# sinket.net
KiCad netlist of a schematic drawn in EAGLE
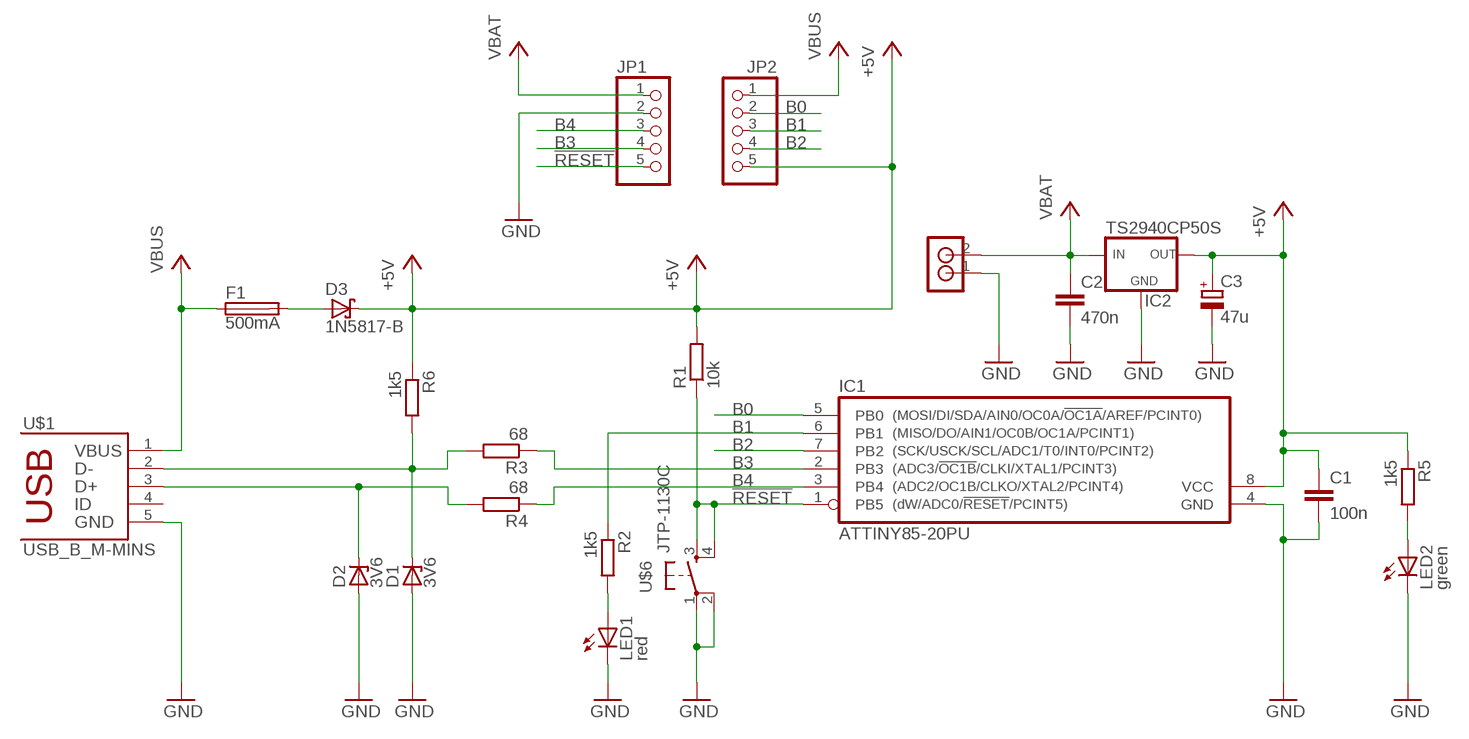
[diagram p0: schematic, sheet 1]

(export (version "E")
  (design (tool "Eeschema 10.0.6"))
  (components
    (comp (ref "C1")
      (value "100n")
      (footprint "eagle-import:C1206")
      (libsource (lib "eagle-import") (part "C-EUC1206"))
    )
    (comp (ref "C2")
      (value "470n")
      (footprint "eagle-import:C025-030X050")
      (libsource (lib "eagle-import") (part "C-EU025-030X050"))
    )
    (comp (ref "C3")
      (value "47u")
      (footprint "eagle-import:E2,5-6")
      (libsource (lib "eagle-import") (part "CPOL-EUE2.5-6"))
    )
    (comp (ref "D1")
      (value "3V6")
      (footprint "eagle-import:SOD80C")
      (libsource (lib "eagle-import") (part "ZENER-DIODESOD80C"))
    )
    (comp (ref "D2")
      (value "3V6")
      (footprint "eagle-import:SOD80C")
      (libsource (lib "eagle-import") (part "ZENER-DIODESOD80C"))
    )
    (comp (ref "D3")
      (value "1N5817-B")
      (footprint "eagle-import:DO41-7.6")
      (libsource (lib "eagle-import") (part "1N5817-B"))
    )
    (comp (ref "F1")
      (value "500mA")
      (footprint "eagle-import:LP60-050")
      (libsource (lib "eagle-import") (part "PTC-FUSE-LP60-050"))
    )
    (comp (ref "IC1")
      (value "ATTINY85-20PU")
      (footprint "eagle-import:8P3")
      (libsource (lib "eagle-import") (part "ATTINY25PU-20"))
    )
    (comp (ref "IC2")
      (value "TS2940CP50S")
      (footprint "eagle-import:TO-252")
      (libsource (lib "eagle-import") (part "TS2940SCP50"))
    )
    (comp (ref "JP1")
      (value "PINHD-1X5")
      (footprint "eagle-import:1X05")
      (libsource (lib "eagle-import") (part "PINHD-1X5"))
    )
    (comp (ref "JP2")
      (value "PINHD-1X5")
      (footprint "eagle-import:1X05")
      (libsource (lib "eagle-import") (part "PINHD-1X5"))
    )
    (comp (ref "LED1")
      (value "red")
      (footprint "eagle-import:LED5MM")
      (libsource (lib "eagle-import") (part "LED5MM"))
    )
    (comp (ref "LED2")
      (value "green")
      (footprint "eagle-import:LED5MM")
      (libsource (lib "eagle-import") (part "LED5MM"))
    )
    (comp (ref "R1")
      (value "10k")
      (footprint "eagle-import:R1206")
      (libsource (lib "eagle-import") (part "R-EU_R1206"))
    )
    (comp (ref "R2")
      (value "1k5")
      (footprint "eagle-import:R1206")
      (libsource (lib "eagle-import") (part "R-EU_R1206"))
    )
    (comp (ref "R3")
      (value "68")
      (footprint "eagle-import:R1206")
      (libsource (lib "eagle-import") (part "R-EU_R1206"))
    )
    (comp (ref "R4")
      (value "68")
      (footprint "eagle-import:R1206")
      (libsource (lib "eagle-import") (part "R-EU_R1206"))
    )
    (comp (ref "R5")
      (value "1k5")
      (footprint "eagle-import:R1206")
      (libsource (lib "eagle-import") (part "R-EU_R1206"))
    )
    (comp (ref "R6")
      (value "1k5")
      (footprint "eagle-import:R1206")
      (libsource (lib "eagle-import") (part "R-EU_R1206"))
    )
    (comp (ref "U$1")
      (value "USB_B_M-MINS")
      (footprint "eagle-import:LUMBERG_2486-01")
      (libsource (lib "eagle-import") (part "USB_B_M-MINS"))
    )
    (comp (ref "U$6")
      (value "JTP-1130C")
      (footprint "eagle-import:JTP-1130")
      (libsource (lib "eagle-import") (part "JTP-1130C"))
    )
    (comp (ref "U$7")
      (value "RIACON_101_2")
      (footprint "eagle-import:RIACON_101_2")
      (libsource (lib "eagle-import") (part "RIACON_101_2"))
    )
  )
  (nets
    (net (code "1") (name "+5V") (class "Default")
      (node (ref "C1") (pin "1") (pinfunction "1_1") (pintype "passive"))
      (node (ref "C3") (pin "+") (pinfunction "+_+") (pintype "passive"))
      (node (ref "D3") (pin "C") (pinfunction "C_C") (pintype "passive"))
      (node (ref "IC1") (pin "8") (pinfunction "VCC_8") (pintype "power_in"))
      (node (ref "IC2") (pin "3") (pinfunction "OUT_3") (pintype "power_in"))
      (node (ref "JP2") (pin "5") (pinfunction "5_5") (pintype "passive"))
      (node (ref "R1") (pin "2") (pinfunction "2_2") (pintype "passive"))
      (node (ref "R5") (pin "1") (pinfunction "1_1") (pintype "passive"))
      (node (ref "R6") (pin "1") (pinfunction "1_1") (pintype "passive"))
    )
    (net (code "2") (name "/B0") (class "Default")
      (node (ref "IC1") (pin "5") (pinfunction "PB0_5") (pintype "bidirectional"))
      (node (ref "JP2") (pin "2") (pinfunction "2_2") (pintype "passive"))
    )
    (net (code "3") (name "/B1") (class "Default")
      (node (ref "IC1") (pin "6") (pinfunction "PB1_6") (pintype "bidirectional"))
      (node (ref "JP2") (pin "3") (pinfunction "3_3") (pintype "passive"))
      (node (ref "R2") (pin "1") (pinfunction "1_1") (pintype "passive"))
    )
    (net (code "4") (name "/B2") (class "Default")
      (node (ref "IC1") (pin "7") (pinfunction "PB2_7") (pintype "bidirectional"))
      (node (ref "JP2") (pin "4") (pinfunction "4_4") (pintype "passive"))
    )
    (net (code "5") (name "/B3") (class "Default")
      (node (ref "IC1") (pin "2") (pinfunction "PB3_2") (pintype "bidirectional"))
      (node (ref "JP1") (pin "4") (pinfunction "4_4") (pintype "passive"))
      (node (ref "R3") (pin "1") (pinfunction "1_1") (pintype "passive"))
    )
    (net (code "6") (name "/B4") (class "Default")
      (node (ref "IC1") (pin "3") (pinfunction "PB4_3") (pintype "bidirectional"))
      (node (ref "JP1") (pin "3") (pinfunction "3_3") (pintype "passive"))
      (node (ref "R4") (pin "1") (pinfunction "1_1") (pintype "passive"))
    )
    (net (code "7") (name "/~{RESET}") (class "Default")
      (node (ref "IC1") (pin "1") (pinfunction "PB5_1") (pintype "bidirectional"))
      (node (ref "JP1") (pin "5") (pinfunction "5_5") (pintype "passive"))
      (node (ref "R1") (pin "1") (pinfunction "1_1") (pintype "passive"))
      (node (ref "U$6") (pin "3") (pinfunction "S_3") (pintype "passive"))
      (node (ref "U$6") (pin "4") (pinfunction "S1_4") (pintype "passive"))
    )
    (net (code "8") (name "GND") (class "Default")
      (node (ref "C1") (pin "2") (pinfunction "2_2") (pintype "passive"))
      (node (ref "C2") (pin "2") (pinfunction "2_2") (pintype "passive"))
      (node (ref "C3") (pin "-") (pinfunction "-_-") (pintype "passive"))
      (node (ref "D1") (pin "A") (pinfunction "A_A") (pintype "passive"))
      (node (ref "D2") (pin "A") (pinfunction "A_A") (pintype "passive"))
      (node (ref "IC1") (pin "4") (pinfunction "GND_4") (pintype "power_in"))
      (node (ref "IC2") (pin "2") (pinfunction "GND_2") (pintype "power_in"))
      (node (ref "JP1") (pin "2") (pinfunction "2_2") (pintype "passive"))
      (node (ref "LED1") (pin "K") (pinfunction "C_K") (pintype "passive"))
      (node (ref "LED2") (pin "K") (pinfunction "C_K") (pintype "passive"))
      (node (ref "U$1") (pin "5") (pinfunction "5_5") (pintype "passive"))
      (node (ref "U$6") (pin "1") (pinfunction "P_1") (pintype "passive"))
      (node (ref "U$6") (pin "2") (pinfunction "P1_2") (pintype "passive"))
      (node (ref "U$7") (pin "1") (pinfunction "1_1") (pintype "passive"))
    )
    (net (code "9") (name "Net-(D1-PadC)") (class "Default")
      (node (ref "D1") (pin "C") (pinfunction "C_C") (pintype "passive"))
      (node (ref "R3") (pin "2") (pinfunction "2_2") (pintype "passive"))
      (node (ref "R6") (pin "2") (pinfunction "2_2") (pintype "passive"))
      (node (ref "U$1") (pin "2") (pinfunction "2_2") (pintype "passive"))
    )
    (net (code "10") (name "Net-(D2-PadC)") (class "Default")
      (node (ref "D2") (pin "C") (pinfunction "C_C") (pintype "passive"))
      (node (ref "R4") (pin "2") (pinfunction "2_2") (pintype "passive"))
      (node (ref "U$1") (pin "3") (pinfunction "3_3") (pintype "passive"))
    )
    (net (code "11") (name "Net-(F1-2)") (class "Default")
      (node (ref "D3") (pin "A") (pinfunction "A_A") (pintype "passive"))
      (node (ref "F1") (pin "P$2") (pinfunction "2_P$2") (pintype "passive"))
    )
    (net (code "12") (name "Net-(LED1-PadA)") (class "Default")
      (node (ref "LED1") (pin "A") (pinfunction "A_A") (pintype "passive"))
      (node (ref "R2") (pin "2") (pinfunction "2_2") (pintype "passive"))
    )
    (net (code "13") (name "Net-(LED2-PadA)") (class "Default")
      (node (ref "LED2") (pin "A") (pinfunction "A_A") (pintype "passive"))
      (node (ref "R5") (pin "2") (pinfunction "2_2") (pintype "passive"))
    )
    (net (code "14") (name "VBAT") (class "Default")
      (node (ref "C2") (pin "1") (pinfunction "1_1") (pintype "passive"))
      (node (ref "IC2") (pin "1") (pinfunction "IN_1") (pintype "power_in"))
      (node (ref "JP1") (pin "1") (pinfunction "1_1") (pintype "passive"))
      (node (ref "U$7") (pin "2") (pinfunction "2_2") (pintype "passive"))
    )
    (net (code "15") (name "VBUS") (class "Default")
      (node (ref "F1") (pin "P$1") (pinfunction "1_P$1") (pintype "passive"))
      (node (ref "JP2") (pin "1") (pinfunction "1_1") (pintype "passive"))
      (node (ref "U$1") (pin "1") (pinfunction "1_1") (pintype "passive"))
    )
    (net (code "16") (name "unconnected-(U$1-Pad4)") (class "Default")
      (node (ref "U$1") (pin "4") (pinfunction "4_4") (pintype "passive"))
    )
  )
)
